# PIC32MZ_Bare_Bones.net
KiCad netlist of a schematic drawn in EAGLE
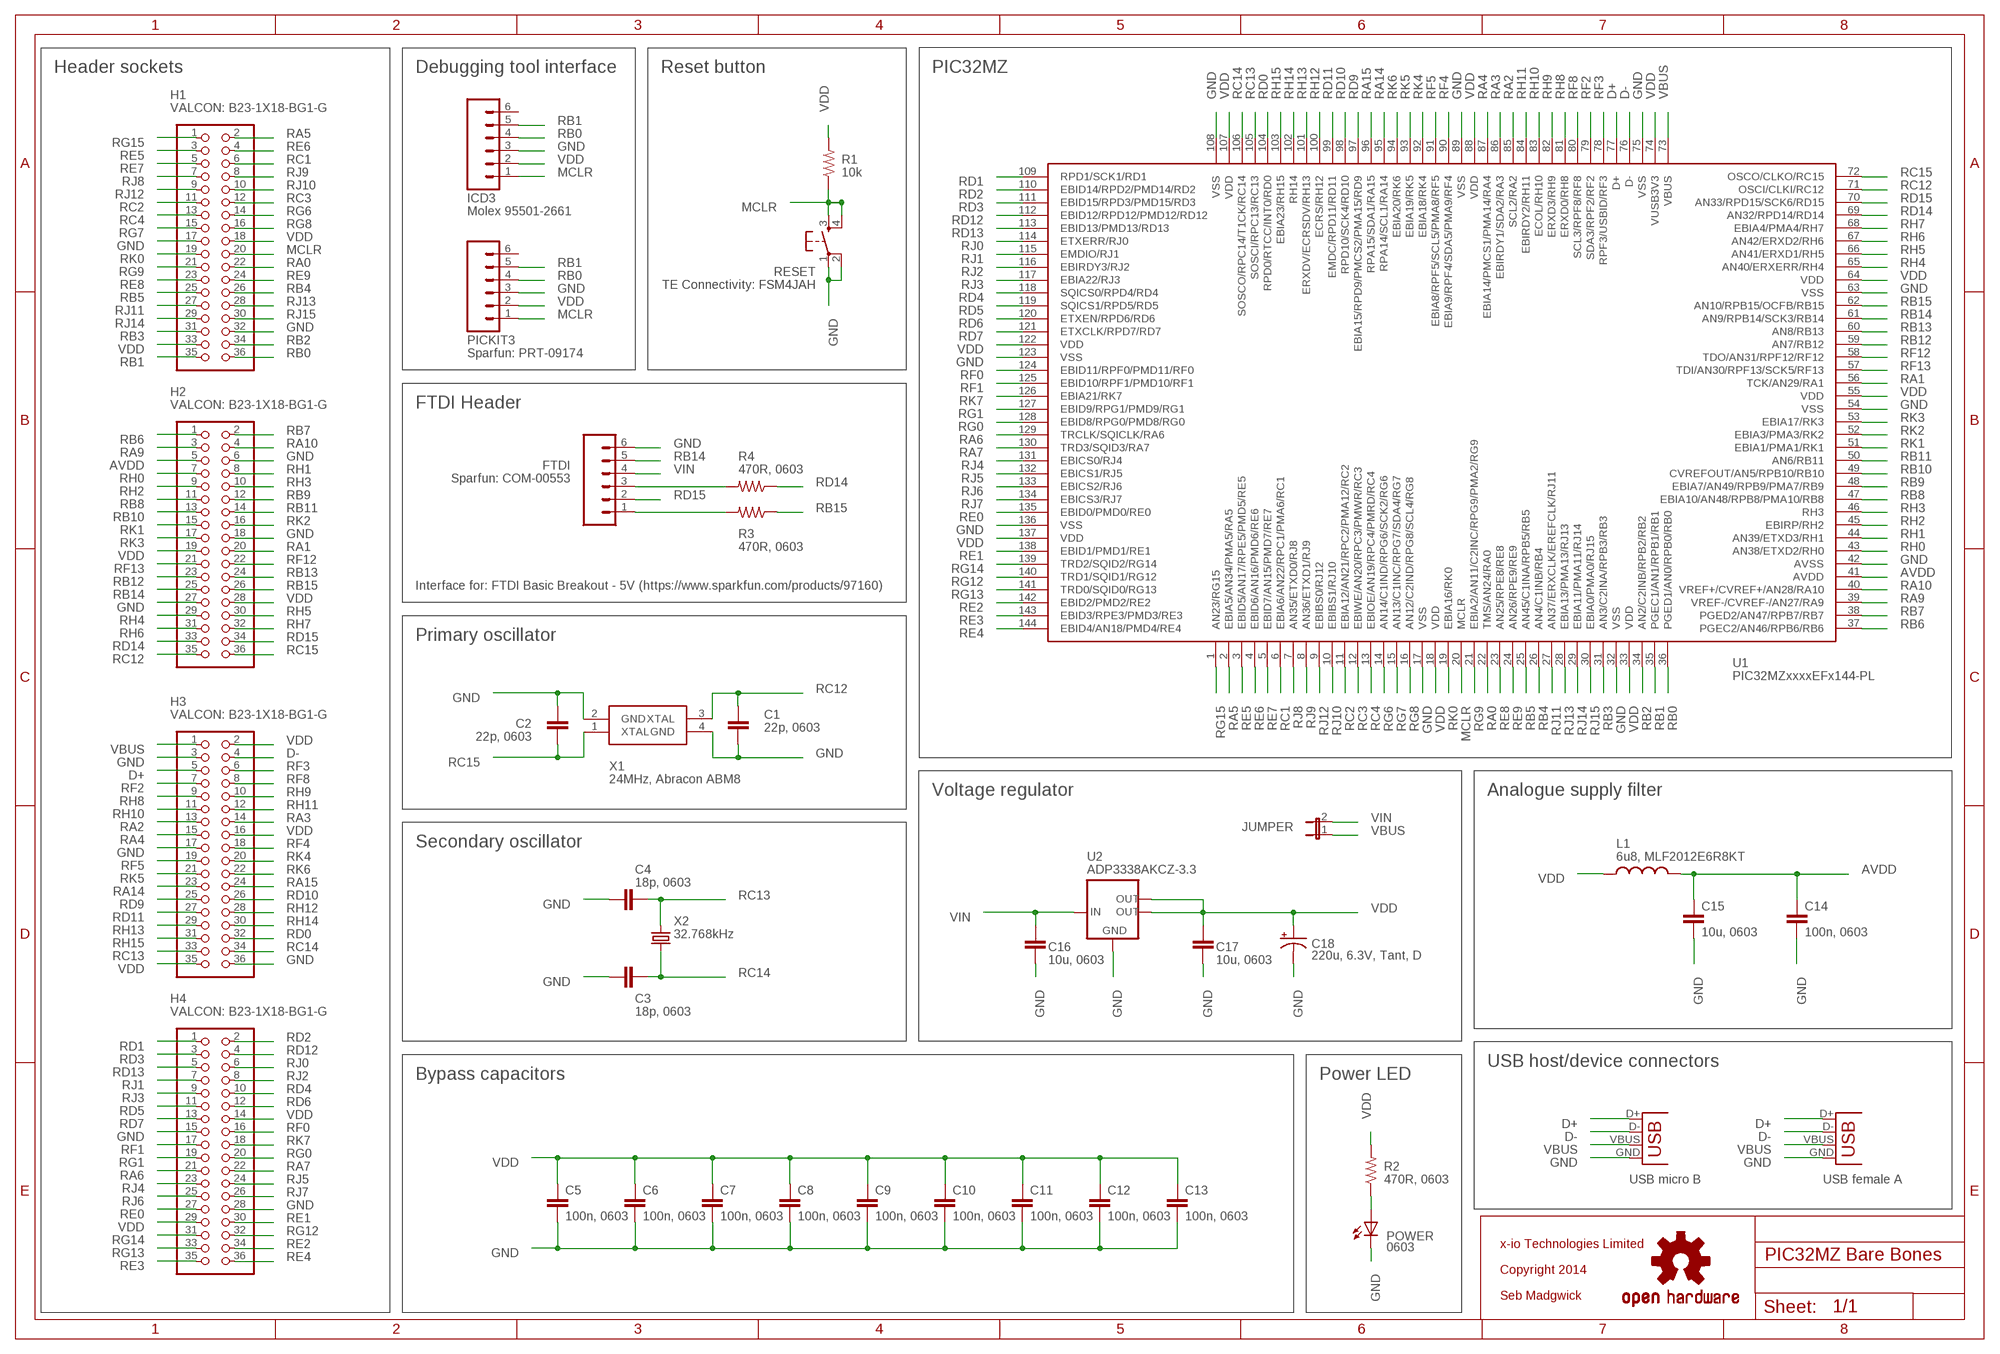
[diagram p0: schematic, sheet 1]

(export (version "E")
  (design (tool "Eeschema 10.0.6"))
  (components
    (comp (ref "C1")
      (value "22p, 0603")
      (footprint "eagle-import:0603-CAP")
      (libsource (lib "eagle-import") (part "CAP0603-CAP"))
    )
    (comp (ref "C2")
      (value "22p, 0603")
      (footprint "eagle-import:0603-CAP")
      (libsource (lib "eagle-import") (part "CAP0603-CAP"))
    )
    (comp (ref "C3")
      (value "18p, 0603")
      (footprint "eagle-import:0603-CAP")
      (libsource (lib "eagle-import") (part "CAP0603-CAP"))
    )
    (comp (ref "C4")
      (value "18p, 0603")
      (footprint "eagle-import:0603-CAP")
      (libsource (lib "eagle-import") (part "CAP0603-CAP"))
    )
    (comp (ref "C5")
      (value "100n, 0603")
      (footprint "eagle-import:0603-CAP")
      (libsource (lib "eagle-import") (part "CAP0603-CAP"))
    )
    (comp (ref "C6")
      (value "100n, 0603")
      (footprint "eagle-import:0603-CAP")
      (libsource (lib "eagle-import") (part "CAP0603-CAP"))
    )
    (comp (ref "C7")
      (value "100n, 0603")
      (footprint "eagle-import:0603-CAP")
      (libsource (lib "eagle-import") (part "CAP0603-CAP"))
    )
    (comp (ref "C8")
      (value "100n, 0603")
      (footprint "eagle-import:0603-CAP")
      (libsource (lib "eagle-import") (part "CAP0603-CAP"))
    )
    (comp (ref "C9")
      (value "100n, 0603")
      (footprint "eagle-import:0603-CAP")
      (libsource (lib "eagle-import") (part "CAP0603-CAP"))
    )
    (comp (ref "C10")
      (value "100n, 0603")
      (footprint "eagle-import:0603-CAP")
      (libsource (lib "eagle-import") (part "CAP0603-CAP"))
    )
    (comp (ref "C11")
      (value "100n, 0603")
      (footprint "eagle-import:0603-CAP")
      (libsource (lib "eagle-import") (part "CAP0603-CAP"))
    )
    (comp (ref "C12")
      (value "100n, 0603")
      (footprint "eagle-import:0603-CAP")
      (libsource (lib "eagle-import") (part "CAP0603-CAP"))
    )
    (comp (ref "C13")
      (value "100n, 0603")
      (footprint "eagle-import:0603-CAP")
      (libsource (lib "eagle-import") (part "CAP0603-CAP"))
    )
    (comp (ref "C14")
      (value "100n, 0603")
      (footprint "eagle-import:0603-CAP")
      (libsource (lib "eagle-import") (part "CAP0603-CAP"))
    )
    (comp (ref "C15")
      (value "10u, 0603")
      (footprint "eagle-import:0603-CAP")
      (libsource (lib "eagle-import") (part "CAP0603-CAP"))
    )
    (comp (ref "C16")
      (value "10u, 0603")
      (footprint "eagle-import:0603-CAP")
      (libsource (lib "eagle-import") (part "CAP0603-CAP"))
    )
    (comp (ref "C17")
      (value "10u, 0603")
      (footprint "eagle-import:0603-CAP")
      (libsource (lib "eagle-import") (part "CAP0603-CAP"))
    )
    (comp (ref "C18")
      (value "220u, 6.3V, Tant, D")
      (footprint "eagle-import:SMC_D")
      (libsource (lib "eagle-import") (part "CPOL-USSMCD"))
    )
    (comp (ref "FTDI")
      (value "Sparfun: COM-00553")
      (footprint "eagle-import:1X06")
      (libsource (lib "eagle-import") (part "M06SIP"))
    )
    (comp (ref "H1")
      (value "VALCON: B23-1X18-BG1-G")
      (footprint "eagle-import:2X18")
      (libsource (lib "eagle-import") (part "PINHD-2X18"))
    )
    (comp (ref "H2")
      (value "VALCON: B23-1X18-BG1-G")
      (footprint "eagle-import:2X18")
      (libsource (lib "eagle-import") (part "PINHD-2X18"))
    )
    (comp (ref "H3")
      (value "VALCON: B23-1X18-BG1-G")
      (footprint "eagle-import:2X18")
      (libsource (lib "eagle-import") (part "PINHD-2X18"))
    )
    (comp (ref "H4")
      (value "VALCON: B23-1X18-BG1-G")
      (footprint "eagle-import:2X18")
      (libsource (lib "eagle-import") (part "PINHD-2X18"))
    )
    (comp (ref "ICD3")
      (value "Molex 95501-2661")
      (footprint "eagle-import:RJ11-6")
      (libsource (lib "eagle-import") (part "RJ11-6PTH"))
    )
    (comp (ref "JUMPER")
      (value "JUMPER-2SMD-NO")
      (footprint "eagle-import:SJ_2S-NO")
      (libsource (lib "eagle-import") (part "JUMPER-2SMD-NO"))
    )
    (comp (ref "L1")
      (value "6u8, MLF2012E6R8KT")
      (footprint "eagle-import:1007")
      (libsource (lib "eagle-import") (part "INDUCTOR1007"))
    )
    (comp (ref "PICKIT3")
      (value "Sparfun: PRT-09174")
      (footprint "eagle-import:1X06")
      (libsource (lib "eagle-import") (part "M06SIP"))
    )
    (comp (ref "POWER")
      (value "0603")
      (footprint "eagle-import:LED-0603")
      (libsource (lib "eagle-import") (part "LED0603"))
    )
    (comp (ref "R1")
      (value "10k")
      (footprint "eagle-import:0603-RES")
      (libsource (lib "eagle-import") (part "RESISTOR0603-RES"))
    )
    (comp (ref "R2")
      (value "470R, 0603")
      (footprint "eagle-import:0603-RES")
      (libsource (lib "eagle-import") (part "RESISTOR0603-RES"))
    )
    (comp (ref "R3")
      (value "470R, 0603")
      (footprint "eagle-import:0603-RES")
      (libsource (lib "eagle-import") (part "RESISTOR0603-RES"))
    )
    (comp (ref "R4")
      (value "470R, 0603")
      (footprint "eagle-import:0603-RES")
      (libsource (lib "eagle-import") (part "RESISTOR0603-RES"))
    )
    (comp (ref "RESET")
      (value "TE Connectivity: FSM4JAH")
      (footprint "eagle-import:TACTILE-PTH")
      (libsource (lib "eagle-import") (part "TAC_SWITCHPTH"))
    )
    (comp (ref "U$4")
      (value "OSHW-LOGOS")
      (footprint "eagle-import:OSHW-LOGO-S")
      (libsource (lib "eagle-import") (part "OSHW-LOGOS"))
    )
    (comp (ref "U1")
      (value "PIC32MZxxxxEFx144-PL")
      (footprint "eagle-import:LQFP144")
      (libsource (lib "eagle-import") (part "PIC32MZ2048EC(G/H/M)144-PL"))
    )
    (comp (ref "U2")
      (value "ADP3338AKCZ-3.3")
      (footprint "eagle-import:SOT223")
      (libsource (lib "eagle-import") (part "ADP3338"))
    )
    (comp (ref "X1")
      (value "24MHz, Abracon ABM8")
      (footprint "eagle-import:ABM8")
      (libsource (lib "eagle-import") (part "ABM8"))
    )
    (comp (ref "X2")
      (value "32.768kHz")
      (footprint "eagle-import:TC26H")
      (libsource (lib "eagle-import") (part "CRYSTALTC26H"))
    )
    (comp (ref "X3")
      (value "USB-MICROB")
      (footprint "eagle-import:USB-MICROB")
      (libsource (lib "eagle-import") (part "USB-MICROB"))
    )
    (comp (ref "X4")
      (value "USB-A-SMD")
      (footprint "eagle-import:USB-A-S-NOSILK-FEMALE")
      (libsource (lib "eagle-import") (part "USB-A-SMD"))
    )
  )
  (nets
    (net (code "1") (name "/AVDD") (class "Default")
      (node (ref "C14") (pin "1") (pinfunction "1_1") (pintype "passive"))
      (node (ref "C15") (pin "1") (pinfunction "1_1") (pintype "passive"))
      (node (ref "H2") (pin "5") (pinfunction "5_5") (pintype "passive"))
      (node (ref "L1") (pin "2") (pinfunction "2_2") (pintype "passive"))
      (node (ref "U1") (pin "41") (pinfunction "AVDD_41") (pintype "bidirectional"))
    )
    (net (code "2") (name "/D+") (class "Default")
      (node (ref "H3") (pin "5") (pinfunction "5_5") (pintype "passive"))
      (node (ref "U1") (pin "77") (pinfunction "D+_77") (pintype "bidirectional"))
      (node (ref "X3") (pin "D+") (pinfunction "D+_D+") (pintype "bidirectional"))
      (node (ref "X4") (pin "D+") (pinfunction "D+_D+") (pintype "bidirectional"))
    )
    (net (code "3") (name "/D-") (class "Default")
      (node (ref "H3") (pin "4") (pinfunction "4_4") (pintype "passive"))
      (node (ref "U1") (pin "76") (pinfunction "D-_76") (pintype "bidirectional"))
      (node (ref "X3") (pin "D-") (pinfunction "D-_D-") (pintype "bidirectional"))
      (node (ref "X4") (pin "D-") (pinfunction "D-_D-") (pintype "bidirectional"))
    )
    (net (code "4") (name "/GND") (class "Default")
      (node (ref "C1") (pin "2") (pinfunction "2_2") (pintype "passive"))
      (node (ref "C10") (pin "2") (pinfunction "2_2") (pintype "passive"))
      (node (ref "C11") (pin "2") (pinfunction "2_2") (pintype "passive"))
      (node (ref "C12") (pin "2") (pinfunction "2_2") (pintype "passive"))
      (node (ref "C13") (pin "2") (pinfunction "2_2") (pintype "passive"))
      (node (ref "C14") (pin "2") (pinfunction "2_2") (pintype "passive"))
      (node (ref "C15") (pin "2") (pinfunction "2_2") (pintype "passive"))
      (node (ref "C16") (pin "2") (pinfunction "2_2") (pintype "passive"))
      (node (ref "C17") (pin "2") (pinfunction "2_2") (pintype "passive"))
      (node (ref "C18") (pin "-") (pinfunction "-_-") (pintype "passive"))
      (node (ref "C2") (pin "1") (pinfunction "1_1") (pintype "passive"))
      (node (ref "C3") (pin "2") (pinfunction "2_2") (pintype "passive"))
      (node (ref "C4") (pin "2") (pinfunction "2_2") (pintype "passive"))
      (node (ref "C5") (pin "2") (pinfunction "2_2") (pintype "passive"))
      (node (ref "C6") (pin "2") (pinfunction "2_2") (pintype "passive"))
      (node (ref "C7") (pin "2") (pinfunction "2_2") (pintype "passive"))
      (node (ref "C8") (pin "2") (pinfunction "2_2") (pintype "passive"))
      (node (ref "C9") (pin "2") (pinfunction "2_2") (pintype "passive"))
      (node (ref "FTDI") (pin "6") (pinfunction "6_6") (pintype "passive"))
      (node (ref "H1") (pin "17") (pinfunction "17_17") (pintype "passive"))
      (node (ref "H1") (pin "32") (pinfunction "32_32") (pintype "passive"))
      (node (ref "H2") (pin "18") (pinfunction "18_18") (pintype "passive"))
      (node (ref "H2") (pin "27") (pinfunction "27_27") (pintype "passive"))
      (node (ref "H2") (pin "6") (pinfunction "6_6") (pintype "passive"))
      (node (ref "H3") (pin "17") (pinfunction "17_17") (pintype "passive"))
      (node (ref "H3") (pin "3") (pinfunction "3_3") (pintype "passive"))
      (node (ref "H3") (pin "36") (pinfunction "36_36") (pintype "passive"))
      (node (ref "H4") (pin "15") (pinfunction "15_15") (pintype "passive"))
      (node (ref "H4") (pin "28") (pinfunction "28_28") (pintype "passive"))
      (node (ref "ICD3") (pin "3") (pinfunction "3_3") (pintype "passive"))
      (node (ref "PICKIT3") (pin "3") (pinfunction "3_3") (pintype "passive"))
      (node (ref "POWER") (pin "C") (pinfunction "C_C") (pintype "passive"))
      (node (ref "RESET") (pin "1") (pinfunction "1_1") (pintype "passive"))
      (node (ref "RESET") (pin "2") (pinfunction "2_2") (pintype "passive"))
      (node (ref "U1") (pin "108") (pinfunction "VSS_108") (pintype "bidirectional"))
      (node (ref "U1") (pin "123") (pinfunction "VSS_123") (pintype "bidirectional"))
      (node (ref "U1") (pin "136") (pinfunction "VSS_136") (pintype "bidirectional"))
      (node (ref "U1") (pin "17") (pinfunction "VSS_17") (pintype "bidirectional"))
      (node (ref "U1") (pin "32") (pinfunction "VSS_32") (pintype "bidirectional"))
      (node (ref "U1") (pin "42") (pinfunction "AVSS_42") (pintype "bidirectional"))
      (node (ref "U1") (pin "54") (pinfunction "VSS_54") (pintype "bidirectional"))
      (node (ref "U1") (pin "63") (pinfunction "VSS_63") (pintype "bidirectional"))
      (node (ref "U1") (pin "75") (pinfunction "VSS_75") (pintype "bidirectional"))
      (node (ref "U1") (pin "89") (pinfunction "VSS_89") (pintype "bidirectional"))
      (node (ref "U2") (pin "1") (pinfunction "GND_1") (pintype "input"))
      (node (ref "X1") (pin "2") (pinfunction "GND_2") (pintype "bidirectional"))
      (node (ref "X1") (pin "4") (pinfunction "GND_4") (pintype "bidirectional"))
      (node (ref "X3") (pin "GND") (pinfunction "GND_GND") (pintype "bidirectional"))
      (node (ref "X4") (pin "GND") (pinfunction "GND_GND") (pintype "bidirectional"))
    )
    (net (code "5") (name "/MCLR") (class "Default")
      (node (ref "H1") (pin "20") (pinfunction "20_20") (pintype "passive"))
      (node (ref "ICD3") (pin "1") (pinfunction "1_1") (pintype "passive"))
      (node (ref "PICKIT3") (pin "1") (pinfunction "1_1") (pintype "passive"))
      (node (ref "R1") (pin "1") (pinfunction "1_1") (pintype "passive"))
      (node (ref "RESET") (pin "3") (pinfunction "3_3") (pintype "passive"))
      (node (ref "RESET") (pin "4") (pinfunction "4_4") (pintype "passive"))
      (node (ref "U1") (pin "20") (pinfunction "MCLR_20") (pintype "bidirectional"))
    )
    (net (code "6") (name "/RA0") (class "Default")
      (node (ref "H1") (pin "22") (pinfunction "22_22") (pintype "passive"))
      (node (ref "U1") (pin "22") (pinfunction "TMS/AN24/RA0_22") (pintype "bidirectional"))
    )
    (net (code "7") (name "/RA1") (class "Default")
      (node (ref "H2") (pin "20") (pinfunction "20_20") (pintype "passive"))
      (node (ref "U1") (pin "56") (pinfunction "TCK/AN29/RA1_56") (pintype "bidirectional"))
    )
    (net (code "8") (name "/RA2") (class "Default")
      (node (ref "H3") (pin "13") (pinfunction "13_13") (pintype "passive"))
      (node (ref "U1") (pin "85") (pinfunction "SCL2/RA2_85") (pintype "bidirectional"))
    )
    (net (code "9") (name "/RA3") (class "Default")
      (node (ref "H3") (pin "14") (pinfunction "14_14") (pintype "passive"))
      (node (ref "U1") (pin "86") (pinfunction "EBIRDY1/SDA2/RA3_86") (pintype "bidirectional"))
    )
    (net (code "10") (name "/RA4") (class "Default")
      (node (ref "H3") (pin "15") (pinfunction "15_15") (pintype "passive"))
      (node (ref "U1") (pin "87") (pinfunction "EBIA14/PMCS1/PMA14/RA4_87") (pintype "bidirectional"))
    )
    (net (code "11") (name "/RA5") (class "Default")
      (node (ref "H1") (pin "2") (pinfunction "2_2") (pintype "passive"))
      (node (ref "U1") (pin "2") (pinfunction "EBIA5/AN34/PMA5/RA5_2") (pintype "bidirectional"))
    )
    (net (code "12") (name "/RA6") (class "Default")
      (node (ref "H4") (pin "21") (pinfunction "21_21") (pintype "passive"))
      (node (ref "U1") (pin "129") (pinfunction "TRCLK/SQICLK/RA6_129") (pintype "bidirectional"))
    )
    (net (code "13") (name "/RA7") (class "Default")
      (node (ref "H4") (pin "22") (pinfunction "22_22") (pintype "passive"))
      (node (ref "U1") (pin "130") (pinfunction "TRD3/SQID3/RA7_130") (pintype "bidirectional"))
    )
    (net (code "14") (name "/RA9") (class "Default")
      (node (ref "H2") (pin "3") (pinfunction "3_3") (pintype "passive"))
      (node (ref "U1") (pin "39") (pinfunction "VREF-/CVREF-/AN27/RA9_39") (pintype "bidirectional"))
    )
    (net (code "15") (name "/RA10") (class "Default")
      (node (ref "H2") (pin "4") (pinfunction "4_4") (pintype "passive"))
      (node (ref "U1") (pin "40") (pinfunction "VREF+/CVREF+/AN28/RA10_40") (pintype "bidirectional"))
    )
    (net (code "16") (name "/RA14") (class "Default")
      (node (ref "H3") (pin "23") (pinfunction "23_23") (pintype "passive"))
      (node (ref "U1") (pin "95") (pinfunction "RPA14/SCL1/RA14_95") (pintype "bidirectional"))
    )
    (net (code "17") (name "/RA15") (class "Default")
      (node (ref "H3") (pin "24") (pinfunction "24_24") (pintype "passive"))
      (node (ref "U1") (pin "96") (pinfunction "RPA15/SDA1/RA15_96") (pintype "bidirectional"))
    )
    (net (code "18") (name "/RB0") (class "Default")
      (node (ref "H1") (pin "36") (pinfunction "36_36") (pintype "passive"))
      (node (ref "ICD3") (pin "4") (pinfunction "4_4") (pintype "passive"))
      (node (ref "PICKIT3") (pin "4") (pinfunction "4_4") (pintype "passive"))
      (node (ref "U1") (pin "36") (pinfunction "PGED1/AN0/RPB0/RB0_36") (pintype "bidirectional"))
    )
    (net (code "19") (name "/RB1") (class "Default")
      (node (ref "H1") (pin "35") (pinfunction "35_35") (pintype "passive"))
      (node (ref "ICD3") (pin "5") (pinfunction "5_5") (pintype "passive"))
      (node (ref "PICKIT3") (pin "5") (pinfunction "5_5") (pintype "passive"))
      (node (ref "U1") (pin "35") (pinfunction "PGEC1/AN1/RPB1/RB1_35") (pintype "bidirectional"))
    )
    (net (code "20") (name "/RB2") (class "Default")
      (node (ref "H1") (pin "34") (pinfunction "34_34") (pintype "passive"))
      (node (ref "U1") (pin "34") (pinfunction "AN2/C2INB/RPB2/RB2_34") (pintype "bidirectional"))
    )
    (net (code "21") (name "/RB3") (class "Default")
      (node (ref "H1") (pin "31") (pinfunction "31_31") (pintype "passive"))
      (node (ref "U1") (pin "31") (pinfunction "AN3/C2INA/RPB3/RB3_31") (pintype "bidirectional"))
    )
    (net (code "22") (name "/RB4") (class "Default")
      (node (ref "H1") (pin "26") (pinfunction "26_26") (pintype "passive"))
      (node (ref "U1") (pin "26") (pinfunction "AN4/C1INB/RB4_26") (pintype "bidirectional"))
    )
    (net (code "23") (name "/RB5") (class "Default")
      (node (ref "H1") (pin "25") (pinfunction "25_25") (pintype "passive"))
      (node (ref "U1") (pin "25") (pinfunction "AN45/C1INA/RPB5/RB5_25") (pintype "bidirectional"))
    )
    (net (code "24") (name "/RB6") (class "Default")
      (node (ref "H2") (pin "1") (pinfunction "1_1") (pintype "passive"))
      (node (ref "U1") (pin "37") (pinfunction "PGEC2/AN46/RPB6/RB6_37") (pintype "bidirectional"))
    )
    (net (code "25") (name "/RB7") (class "Default")
      (node (ref "H2") (pin "2") (pinfunction "2_2") (pintype "passive"))
      (node (ref "U1") (pin "38") (pinfunction "PGED2/AN47/RPB7/RB7_38") (pintype "bidirectional"))
    )
    (net (code "26") (name "/RB8") (class "Default")
      (node (ref "H2") (pin "11") (pinfunction "11_11") (pintype "passive"))
      (node (ref "U1") (pin "47") (pinfunction "EBIA10/AN48/RPB8/PMA10/RB8_47") (pintype "bidirectional"))
    )
    (net (code "27") (name "/RB9") (class "Default")
      (node (ref "H2") (pin "12") (pinfunction "12_12") (pintype "passive"))
      (node (ref "U1") (pin "48") (pinfunction "EBIA7/AN49/RPB9/PMA7/RB9_48") (pintype "bidirectional"))
    )
    (net (code "28") (name "/RB10") (class "Default")
      (node (ref "H2") (pin "13") (pinfunction "13_13") (pintype "passive"))
      (node (ref "U1") (pin "49") (pinfunction "CVREFOUT/AN5/RPB10/RB10_49") (pintype "bidirectional"))
    )
    (net (code "29") (name "/RB11") (class "Default")
      (node (ref "H2") (pin "14") (pinfunction "14_14") (pintype "passive"))
      (node (ref "U1") (pin "50") (pinfunction "AN6/RB11_50") (pintype "bidirectional"))
    )
    (net (code "30") (name "/RB12") (class "Default")
      (node (ref "H2") (pin "23") (pinfunction "23_23") (pintype "passive"))
      (node (ref "U1") (pin "59") (pinfunction "AN7/RB12_59") (pintype "bidirectional"))
    )
    (net (code "31") (name "/RB13") (class "Default")
      (node (ref "H2") (pin "24") (pinfunction "24_24") (pintype "passive"))
      (node (ref "U1") (pin "60") (pinfunction "AN8/RB13_60") (pintype "bidirectional"))
    )
    (net (code "32") (name "/RB14") (class "Default")
      (node (ref "FTDI") (pin "5") (pinfunction "5_5") (pintype "passive"))
      (node (ref "H2") (pin "25") (pinfunction "25_25") (pintype "passive"))
      (node (ref "U1") (pin "61") (pinfunction "AN9/RPB14/SCK3/RB14_61") (pintype "bidirectional"))
    )
    (net (code "33") (name "/RB15") (class "Default")
      (node (ref "H2") (pin "26") (pinfunction "26_26") (pintype "passive"))
      (node (ref "R3") (pin "1") (pinfunction "1_1") (pintype "passive"))
      (node (ref "U1") (pin "62") (pinfunction "AN10/RPB15/OCFB/RB15_62") (pintype "bidirectional"))
    )
    (net (code "34") (name "/RC1") (class "Default")
      (node (ref "H1") (pin "6") (pinfunction "6_6") (pintype "passive"))
      (node (ref "U1") (pin "6") (pinfunction "EBIA6/AN22/RPC1/PMA6/RC1_6") (pintype "bidirectional"))
    )
    (net (code "35") (name "/RC2") (class "Default")
      (node (ref "H1") (pin "11") (pinfunction "11_11") (pintype "passive"))
      (node (ref "U1") (pin "11") (pinfunction "EBIA12/AN21/RPC2/PMA12/RC2_11") (pintype "bidirectional"))
    )
    (net (code "36") (name "/RC3") (class "Default")
      (node (ref "H1") (pin "12") (pinfunction "12_12") (pintype "passive"))
      (node (ref "U1") (pin "12") (pinfunction "EBIWE/AN20/RPC3/PMWR/RC3_12") (pintype "bidirectional"))
    )
    (net (code "37") (name "/RC4") (class "Default")
      (node (ref "H1") (pin "13") (pinfunction "13_13") (pintype "passive"))
      (node (ref "U1") (pin "13") (pinfunction "EBIOE/AN19/RPC4/PMRD/RC4_13") (pintype "bidirectional"))
    )
    (net (code "38") (name "/RC12") (class "Default")
      (node (ref "C1") (pin "1") (pinfunction "1_1") (pintype "passive"))
      (node (ref "H2") (pin "35") (pinfunction "35_35") (pintype "passive"))
      (node (ref "U1") (pin "71") (pinfunction "OSCI/CLKI/RC12_71") (pintype "bidirectional"))
      (node (ref "X1") (pin "3") (pinfunction "XTAL_3") (pintype "bidirectional"))
    )
    (net (code "39") (name "/RC13") (class "Default")
      (node (ref "C4") (pin "1") (pinfunction "1_1") (pintype "passive"))
      (node (ref "H3") (pin "33") (pinfunction "33_33") (pintype "passive"))
      (node (ref "U1") (pin "105") (pinfunction "SOSCI/RPC13/RC13_105") (pintype "bidirectional"))
      (node (ref "X2") (pin "1") (pinfunction "1_1") (pintype "passive"))
    )
    (net (code "40") (name "/RC14") (class "Default")
      (node (ref "C3") (pin "1") (pinfunction "1_1") (pintype "passive"))
      (node (ref "H3") (pin "34") (pinfunction "34_34") (pintype "passive"))
      (node (ref "U1") (pin "106") (pinfunction "SOSCO/RPC14/T1CK/RC14_106") (pintype "bidirectional"))
      (node (ref "X2") (pin "2") (pinfunction "2_2") (pintype "passive"))
    )
    (net (code "41") (name "/RC15") (class "Default")
      (node (ref "C2") (pin "2") (pinfunction "2_2") (pintype "passive"))
      (node (ref "H2") (pin "36") (pinfunction "36_36") (pintype "passive"))
      (node (ref "U1") (pin "72") (pinfunction "OSCO/CLKO/RC15_72") (pintype "bidirectional"))
      (node (ref "X1") (pin "1") (pinfunction "XTAL_1") (pintype "bidirectional"))
    )
    (net (code "42") (name "/RD0") (class "Default")
      (node (ref "H3") (pin "32") (pinfunction "32_32") (pintype "passive"))
      (node (ref "U1") (pin "104") (pinfunction "RPD0/RTCC/INT0/RD0_104") (pintype "bidirectional"))
    )
    (net (code "43") (name "/RD1") (class "Default")
      (node (ref "H4") (pin "1") (pinfunction "1_1") (pintype "passive"))
      (node (ref "U1") (pin "109") (pinfunction "RPD1/SCK1/RD1_109") (pintype "bidirectional"))
    )
    (net (code "44") (name "/RD2") (class "Default")
      (node (ref "H4") (pin "2") (pinfunction "2_2") (pintype "passive"))
      (node (ref "U1") (pin "110") (pinfunction "EBID14/RPD2/PMD14/RD2_110") (pintype "bidirectional"))
    )
    (net (code "45") (name "/RD3") (class "Default")
      (node (ref "H4") (pin "3") (pinfunction "3_3") (pintype "passive"))
      (node (ref "U1") (pin "111") (pinfunction "EBID15/RPD3/PMD15/RD3_111") (pintype "bidirectional"))
    )
    (net (code "46") (name "/RD4") (class "Default")
      (node (ref "H4") (pin "10") (pinfunction "10_10") (pintype "passive"))
      (node (ref "U1") (pin "118") (pinfunction "SQICS0/RPD4/RD4_118") (pintype "bidirectional"))
    )
    (net (code "47") (name "/RD5") (class "Default")
      (node (ref "H4") (pin "11") (pinfunction "11_11") (pintype "passive"))
      (node (ref "U1") (pin "119") (pinfunction "SQICS1/RPD5/RD5_119") (pintype "bidirectional"))
    )
    (net (code "48") (name "/RD6") (class "Default")
      (node (ref "H4") (pin "12") (pinfunction "12_12") (pintype "passive"))
      (node (ref "U1") (pin "120") (pinfunction "ETXEN/RPD6/RD6_120") (pintype "bidirectional"))
    )
    (net (code "49") (name "/RD7") (class "Default")
      (node (ref "H4") (pin "13") (pinfunction "13_13") (pintype "passive"))
      (node (ref "U1") (pin "121") (pinfunction "ETXCLK/RPD7/RD7_121") (pintype "bidirectional"))
    )
    (net (code "50") (name "/RD9") (class "Default")
      (node (ref "H3") (pin "25") (pinfunction "25_25") (pintype "passive"))
      (node (ref "U1") (pin "97") (pinfunction "EBIA15/RPD9/PMCS2/PMA15/RD9_97") (pintype "bidirectional"))
    )
    (net (code "51") (name "/RD10") (class "Default")
      (node (ref "H3") (pin "26") (pinfunction "26_26") (pintype "passive"))
      (node (ref "U1") (pin "98") (pinfunction "RPD10/SCK4/RD10_98") (pintype "bidirectional"))
    )
    (net (code "52") (name "/RD11") (class "Default")
      (node (ref "H3") (pin "27") (pinfunction "27_27") (pintype "passive"))
      (node (ref "U1") (pin "99") (pinfunction "EMDC/RPD11/RD11_99") (pintype "bidirectional"))
    )
    (net (code "53") (name "/RD12") (class "Default")
      (node (ref "H4") (pin "4") (pinfunction "4_4") (pintype "passive"))
      (node (ref "U1") (pin "112") (pinfunction "EBID12/RPD12/PMD12/RD12_112") (pintype "bidirectional"))
    )
    (net (code "54") (name "/RD13") (class "Default")
      (node (ref "H4") (pin "5") (pinfunction "5_5") (pintype "passive"))
      (node (ref "U1") (pin "113") (pinfunction "EBID13/PMD13/RD13_113") (pintype "bidirectional"))
    )
    (net (code "55") (name "/RD14") (class "Default")
      (node (ref "H2") (pin "33") (pinfunction "33_33") (pintype "passive"))
      (node (ref "R4") (pin "1") (pinfunction "1_1") (pintype "passive"))
      (node (ref "U1") (pin "69") (pinfunction "AN32/RPD14/RD14_69") (pintype "bidirectional"))
    )
    (net (code "56") (name "/RD15") (class "Default")
      (node (ref "FTDI") (pin "2") (pinfunction "2_2") (pintype "passive"))
      (node (ref "H2") (pin "34") (pinfunction "34_34") (pintype "passive"))
      (node (ref "U1") (pin "70") (pinfunction "AN33/RPD15/SCK6/RD15_70") (pintype "bidirectional"))
    )
    (net (code "57") (name "/RE0") (class "Default")
      (node (ref "H4") (pin "27") (pinfunction "27_27") (pintype "passive"))
      (node (ref "U1") (pin "135") (pinfunction "EBID0/PMD0/RE0_135") (pintype "bidirectional"))
    )
    (net (code "58") (name "/RE1") (class "Default")
      (node (ref "H4") (pin "30") (pinfunction "30_30") (pintype "passive"))
      (node (ref "U1") (pin "138") (pinfunction "EBID1/PMD1/RE1_138") (pintype "bidirectional"))
    )
    (net (code "59") (name "/RE2") (class "Default")
      (node (ref "H4") (pin "34") (pinfunction "34_34") (pintype "passive"))
      (node (ref "U1") (pin "142") (pinfunction "EBID2/PMD2/RE2_142") (pintype "bidirectional"))
    )
    (net (code "60") (name "/RE3") (class "Default")
      (node (ref "H4") (pin "35") (pinfunction "35_35") (pintype "passive"))
      (node (ref "U1") (pin "143") (pinfunction "EBID3/RPE3/PMD3/RE3_143") (pintype "bidirectional"))
    )
    (net (code "61") (name "/RE4") (class "Default")
      (node (ref "H4") (pin "36") (pinfunction "36_36") (pintype "passive"))
      (node (ref "U1") (pin "144") (pinfunction "EBID4/AN18/PMD4/RE4_144") (pintype "bidirectional"))
    )
    (net (code "62") (name "/RE5") (class "Default")
      (node (ref "H1") (pin "3") (pinfunction "3_3") (pintype "passive"))
      (node (ref "U1") (pin "3") (pinfunction "EBID5/AN17/RPE5/PMD5/RE5_3") (pintype "bidirectional"))
    )
    (net (code "63") (name "/RE6") (class "Default")
      (node (ref "H1") (pin "4") (pinfunction "4_4") (pintype "passive"))
      (node (ref "U1") (pin "4") (pinfunction "EBID6/AN16/PMD6/RE6_4") (pintype "bidirectional"))
    )
    (net (code "64") (name "/RE7") (class "Default")
      (node (ref "H1") (pin "5") (pinfunction "5_5") (pintype "passive"))
      (node (ref "U1") (pin "5") (pinfunction "EBID7/AN15/PMD7/RE7_5") (pintype "bidirectional"))
    )
    (net (code "65") (name "/RE8") (class "Default")
      (node (ref "H1") (pin "23") (pinfunction "23_23") (pintype "passive"))
      (node (ref "U1") (pin "23") (pinfunction "AN25/RPE8/RE8_23") (pintype "bidirectional"))
    )
    (net (code "66") (name "/RE9") (class "Default")
      (node (ref "H1") (pin "24") (pinfunction "24_24") (pintype "passive"))
      (node (ref "U1") (pin "24") (pinfunction "AN26/RPE9/RE9_24") (pintype "bidirectional"))
    )
    (net (code "67") (name "/RF0") (class "Default")
      (node (ref "H4") (pin "16") (pinfunction "16_16") (pintype "passive"))
      (node (ref "U1") (pin "124") (pinfunction "EBID11/RPF0/PMD11/RF0_124") (pintype "bidirectional"))
    )
    (net (code "68") (name "/RF1") (class "Default")
      (node (ref "H4") (pin "17") (pinfunction "17_17") (pintype "passive"))
      (node (ref "U1") (pin "125") (pinfunction "EBID10/RPF1/PMD10/RF1_125") (pintype "bidirectional"))
    )
    (net (code "69") (name "/RF2") (class "Default")
      (node (ref "H3") (pin "7") (pinfunction "7_7") (pintype "passive"))
      (node (ref "U1") (pin "79") (pinfunction "SDA3/RPF2/RF2_79") (pintype "bidirectional"))
    )
    (net (code "70") (name "/RF3") (class "Default")
      (node (ref "H3") (pin "6") (pinfunction "6_6") (pintype "passive"))
      (node (ref "U1") (pin "78") (pinfunction "RPF3/USBID/RF3_78") (pintype "bidirectional"))
    )
    (net (code "71") (name "/RF4") (class "Default")
      (node (ref "H3") (pin "18") (pinfunction "18_18") (pintype "passive"))
      (node (ref "U1") (pin "90") (pinfunction "EBIA9/RPF4/SDA5/PMA9/RF4_90") (pintype "bidirectional"))
    )
    (net (code "72") (name "/RF5") (class "Default")
      (node (ref "H3") (pin "19") (pinfunction "19_19") (pintype "passive"))
      (node (ref "U1") (pin "91") (pinfunction "EBIA8/RPF5/SCL5/PMA8/RF5_91") (pintype "bidirectional"))
    )
    (net (code "73") (name "/RF8") (class "Default")
      (node (ref "H3") (pin "8") (pinfunction "8_8") (pintype "passive"))
      (node (ref "U1") (pin "80") (pinfunction "SCL3/RPF8/RF8_80") (pintype "bidirectional"))
    )
    (net (code "74") (name "/RF12") (class "Default")
      (node (ref "H2") (pin "22") (pinfunction "22_22") (pintype "passive"))
      (node (ref "U1") (pin "58") (pinfunction "TDO/AN31/RPF12/RF12_58") (pintype "bidirectional"))
    )
    (net (code "75") (name "/RF13") (class "Default")
      (node (ref "H2") (pin "21") (pinfunction "21_21") (pintype "passive"))
      (node (ref "U1") (pin "57") (pinfunction "TDI/AN30/RPF13/SCK5/RF13_57") (pintype "bidirectional"))
    )
    (net (code "76") (name "/RG0") (class "Default")
      (node (ref "H4") (pin "20") (pinfunction "20_20") (pintype "passive"))
      (node (ref "U1") (pin "128") (pinfunction "EBID8/RPG0/PMD8/RG0_128") (pintype "bidirectional"))
    )
    (net (code "77") (name "/RG1") (class "Default")
      (node (ref "H4") (pin "19") (pinfunction "19_19") (pintype "passive"))
      (node (ref "U1") (pin "127") (pinfunction "EBID9/RPG1/PMD9/RG1_127") (pintype "bidirectional"))
    )
    (net (code "78") (name "/RG6") (class "Default")
      (node (ref "H1") (pin "14") (pinfunction "14_14") (pintype "passive"))
      (node (ref "U1") (pin "14") (pinfunction "AN14/C1IND/RPG6/SCK2/RG6_14") (pintype "bidirectional"))
    )
    (net (code "79") (name "/RG7") (class "Default")
      (node (ref "H1") (pin "15") (pinfunction "15_15") (pintype "passive"))
      (node (ref "U1") (pin "15") (pinfunction "AN13/C1INC/RPG7/SDA4/RG7_15") (pintype "bidirectional"))
    )
    (net (code "80") (name "/RG8") (class "Default")
      (node (ref "H1") (pin "16") (pinfunction "16_16") (pintype "passive"))
      (node (ref "U1") (pin "16") (pinfunction "AN12/C2IND/RPG8/SCL4/RG8_16") (pintype "bidirectional"))
    )
    (net (code "81") (name "/RG9") (class "Default")
      (node (ref "H1") (pin "21") (pinfunction "21_21") (pintype "passive"))
      (node (ref "U1") (pin "21") (pinfunction "EBIA2/AN11/C2INC/RPG9/PMA2/RG9_21") (pintype "bidirectional"))
    )
    (net (code "82") (name "/RG12") (class "Default")
      (node (ref "H4") (pin "32") (pinfunction "32_32") (pintype "passive"))
      (node (ref "U1") (pin "140") (pinfunction "TRD1/SQID1/RG12_140") (pintype "bidirectional"))
    )
    (net (code "83") (name "/RG13") (class "Default")
      (node (ref "H4") (pin "33") (pinfunction "33_33") (pintype "passive"))
      (node (ref "U1") (pin "141") (pinfunction "TRD0/SQID0/RG13_141") (pintype "bidirectional"))
    )
    (net (code "84") (name "/RG14") (class "Default")
      (node (ref "H4") (pin "31") (pinfunction "31_31") (pintype "passive"))
      (node (ref "U1") (pin "139") (pinfunction "TRD2/SQID2/RG14_139") (pintype "bidirectional"))
    )
    (net (code "85") (name "/RG15") (class "Default")
      (node (ref "H1") (pin "1") (pinfunction "1_1") (pintype "passive"))
      (node (ref "U1") (pin "1") (pinfunction "AN23/RG15_1") (pintype "bidirectional"))
    )
    (net (code "86") (name "/RH0") (class "Default")
      (node (ref "H2") (pin "7") (pinfunction "7_7") (pintype "passive"))
      (node (ref "U1") (pin "43") (pinfunction "AN38/ETXD2/RH0_43") (pintype "bidirectional"))
    )
    (net (code "87") (name "/RH1") (class "Default")
      (node (ref "H2") (pin "8") (pinfunction "8_8") (pintype "passive"))
      (node (ref "U1") (pin "44") (pinfunction "AN39/ETXD3/RH1_44") (pintype "bidirectional"))
    )
    (net (code "88") (name "/RH2") (class "Default")
      (node (ref "H2") (pin "9") (pinfunction "9_9") (pintype "passive"))
      (node (ref "U1") (pin "45") (pinfunction "EBIRP/RH2_45") (pintype "bidirectional"))
    )
    (net (code "89") (name "/RH3") (class "Default")
      (node (ref "H2") (pin "10") (pinfunction "10_10") (pintype "passive"))
      (node (ref "U1") (pin "46") (pinfunction "RH3_46") (pintype "bidirectional"))
    )
    (net (code "90") (name "/RH4") (class "Default")
      (node (ref "H2") (pin "29") (pinfunction "29_29") (pintype "passive"))
      (node (ref "U1") (pin "65") (pinfunction "AN40/ERXERR/RH4_65") (pintype "bidirectional"))
    )
    (net (code "91") (name "/RH5") (class "Default")
      (node (ref "H2") (pin "30") (pinfunction "30_30") (pintype "passive"))
      (node (ref "U1") (pin "66") (pinfunction "AN41/ERXD1/RH5_66") (pintype "bidirectional"))
    )
    (net (code "92") (name "/RH6") (class "Default")
      (node (ref "H2") (pin "31") (pinfunction "31_31") (pintype "passive"))
      (node (ref "U1") (pin "67") (pinfunction "AN42/ERXD2/RH6_67") (pintype "bidirectional"))
    )
    (net (code "93") (name "/RH7") (class "Default")
      (node (ref "H2") (pin "32") (pinfunction "32_32") (pintype "passive"))
      (node (ref "U1") (pin "68") (pinfunction "EBIA4/PMA4/RH7_68") (pintype "bidirectional"))
    )
    (net (code "94") (name "/RH8") (class "Default")
      (node (ref "H3") (pin "9") (pinfunction "9_9") (pintype "passive"))
      (node (ref "U1") (pin "81") (pinfunction "ERXD0/RH8_81") (pintype "bidirectional"))
    )
    (net (code "95") (name "/RH9") (class "Default")
      (node (ref "H3") (pin "10") (pinfunction "10_10") (pintype "passive"))
      (node (ref "U1") (pin "82") (pinfunction "ERXD3/RH9_82") (pintype "bidirectional"))
    )
    (net (code "96") (name "/RH10") (class "Default")
      (node (ref "H3") (pin "11") (pinfunction "11_11") (pintype "passive"))
      (node (ref "U1") (pin "83") (pinfunction "ECOL/RH10_83") (pintype "bidirectional"))
    )
    (net (code "97") (name "/RH11") (class "Default")
      (node (ref "H3") (pin "12") (pinfunction "12_12") (pintype "passive"))
      (node (ref "U1") (pin "84") (pinfunction "EBIRDY2/RH11_84") (pintype "bidirectional"))
    )
    (net (code "98") (name "/RH12") (class "Default")
      (node (ref "H3") (pin "28") (pinfunction "28_28") (pintype "passive"))
      (node (ref "U1") (pin "100") (pinfunction "ECRS/RH12_100") (pintype "bidirectional"))
    )
    (net (code "99") (name "/RH13") (class "Default")
      (node (ref "H3") (pin "29") (pinfunction "29_29") (pintype "passive"))
      (node (ref "U1") (pin "101") (pinfunction "ERXDV/ECRSDV/RH13_101") (pintype "bidirectional"))
    )
    (net (code "100") (name "/RH14") (class "Default")
      (node (ref "H3") (pin "30") (pinfunction "30_30") (pintype "passive"))
      (node (ref "U1") (pin "102") (pinfunction "RH14_102") (pintype "bidirectional"))
    )
    (net (code "101") (name "/RH15") (class "Default")
      (node (ref "H3") (pin "31") (pinfunction "31_31") (pintype "passive"))
      (node (ref "U1") (pin "103") (pinfunction "EBIA23/RH15_103") (pintype "bidirectional"))
    )
    (net (code "102") (name "/RJ0") (class "Default")
      (node (ref "H4") (pin "6") (pinfunction "6_6") (pintype "passive"))
      (node (ref "U1") (pin "114") (pinfunction "ETXERR/RJ0_114") (pintype "bidirectional"))
    )
    (net (code "103") (name "/RJ1") (class "Default")
      (node (ref "H4") (pin "7") (pinfunction "7_7") (pintype "passive"))
      (node (ref "U1") (pin "115") (pinfunction "EMDIO/RJ1_115") (pintype "bidirectional"))
    )
    (net (code "104") (name "/RJ2") (class "Default")
      (node (ref "H4") (pin "8") (pinfunction "8_8") (pintype "passive"))
      (node (ref "U1") (pin "116") (pinfunction "EBIRDY3/RJ2_116") (pintype "bidirectional"))
    )
    (net (code "105") (name "/RJ3") (class "Default")
      (node (ref "H4") (pin "9") (pinfunction "9_9") (pintype "passive"))
      (node (ref "U1") (pin "117") (pinfunction "EBIA22/RJ3_117") (pintype "bidirectional"))
    )
    (net (code "106") (name "/RJ4") (class "Default")
      (node (ref "H4") (pin "23") (pinfunction "23_23") (pintype "passive"))
      (node (ref "U1") (pin "131") (pinfunction "EBICS0/RJ4_131") (pintype "bidirectional"))
    )
    (net (code "107") (name "/RJ5") (class "Default")
      (node (ref "H4") (pin "24") (pinfunction "24_24") (pintype "passive"))
      (node (ref "U1") (pin "132") (pinfunction "EBICS1/RJ5_132") (pintype "bidirectional"))
    )
    (net (code "108") (name "/RJ6") (class "Default")
      (node (ref "H4") (pin "25") (pinfunction "25_25") (pintype "passive"))
      (node (ref "U1") (pin "133") (pinfunction "EBICS2/RJ6_133") (pintype "bidirectional"))
    )
    (net (code "109") (name "/RJ7") (class "Default")
      (node (ref "H4") (pin "26") (pinfunction "26_26") (pintype "passive"))
      (node (ref "U1") (pin "134") (pinfunction "EBICS3/RJ7_134") (pintype "bidirectional"))
    )
    (net (code "110") (name "/RJ8") (class "Default")
      (node (ref "H1") (pin "7") (pinfunction "7_7") (pintype "passive"))
      (node (ref "U1") (pin "7") (pinfunction "AN35/ETXD0/RJ8_7") (pintype "bidirectional"))
    )
    (net (code "111") (name "/RJ9") (class "Default")
      (node (ref "H1") (pin "8") (pinfunction "8_8") (pintype "passive"))
      (node (ref "U1") (pin "8") (pinfunction "AN36/ETXD1/RJ9_8") (pintype "bidirectional"))
    )
    (net (code "112") (name "/RJ10") (class "Default")
      (node (ref "H1") (pin "10") (pinfunction "10_10") (pintype "passive"))
      (node (ref "U1") (pin "10") (pinfunction "EBIBS1/RJ10_10") (pintype "bidirectional"))
    )
    (net (code "113") (name "/RJ11") (class "Default")
      (node (ref "H1") (pin "27") (pinfunction "27_27") (pintype "passive"))
      (node (ref "U1") (pin "27") (pinfunction "AN37/ERXCLK/EREFCLK/RJ11_27") (pintype "bidirectional"))
    )
    (net (code "114") (name "/RJ12") (class "Default")
      (node (ref "H1") (pin "9") (pinfunction "9_9") (pintype "passive"))
      (node (ref "U1") (pin "9") (pinfunction "EBIBS0/RJ12_9") (pintype "bidirectional"))
    )
    (net (code "115") (name "/RJ13") (class "Default")
      (node (ref "H1") (pin "28") (pinfunction "28_28") (pintype "passive"))
      (node (ref "U1") (pin "28") (pinfunction "EBIA13/PMA13/RJ13_28") (pintype "bidirectional"))
    )
    (net (code "116") (name "/RJ14") (class "Default")
      (node (ref "H1") (pin "29") (pinfunction "29_29") (pintype "passive"))
      (node (ref "U1") (pin "29") (pinfunction "EBIA11/PMA11/RJ14_29") (pintype "bidirectional"))
    )
    (net (code "117") (name "/RJ15") (class "Default")
      (node (ref "H1") (pin "30") (pinfunction "30_30") (pintype "passive"))
      (node (ref "U1") (pin "30") (pinfunction "EBIA0/PMA0/RJ15_30") (pintype "bidirectional"))
    )
    (net (code "118") (name "/RK0") (class "Default")
      (node (ref "H1") (pin "19") (pinfunction "19_19") (pintype "passive"))
      (node (ref "U1") (pin "19") (pinfunction "EBIA16/RK0_19") (pintype "bidirectional"))
    )
    (net (code "119") (name "/RK1") (class "Default")
      (node (ref "H2") (pin "15") (pinfunction "15_15") (pintype "passive"))
      (node (ref "U1") (pin "51") (pinfunction "EBIA1/PMA1/RK1_51") (pintype "bidirectional"))
    )
    (net (code "120") (name "/RK2") (class "Default")
      (node (ref "H2") (pin "16") (pinfunction "16_16") (pintype "passive"))
      (node (ref "U1") (pin "52") (pinfunction "EBIA3/PMA3/RK2_52") (pintype "bidirectional"))
    )
    (net (code "121") (name "/RK3") (class "Default")
      (node (ref "H2") (pin "17") (pinfunction "17_17") (pintype "passive"))
      (node (ref "U1") (pin "53") (pinfunction "EBIA17/RK3_53") (pintype "bidirectional"))
    )
    (net (code "122") (name "/RK4") (class "Default")
      (node (ref "H3") (pin "20") (pinfunction "20_20") (pintype "passive"))
      (node (ref "U1") (pin "92") (pinfunction "EBIA18/RK4_92") (pintype "bidirectional"))
    )
    (net (code "123") (name "/RK5") (class "Default")
      (node (ref "H3") (pin "21") (pinfunction "21_21") (pintype "passive"))
      (node (ref "U1") (pin "93") (pinfunction "EBIA19/RK5_93") (pintype "bidirectional"))
    )
    (net (code "124") (name "/RK6") (class "Default")
      (node (ref "H3") (pin "22") (pinfunction "22_22") (pintype "passive"))
      (node (ref "U1") (pin "94") (pinfunction "EBIA20/RK6_94") (pintype "bidirectional"))
    )
    (net (code "125") (name "/RK7") (class "Default")
      (node (ref "H4") (pin "18") (pinfunction "18_18") (pintype "passive"))
      (node (ref "U1") (pin "126") (pinfunction "EBIA21/RK7_126") (pintype "bidirectional"))
    )
    (net (code "126") (name "/VBUS") (class "Default")
      (node (ref "H3") (pin "1") (pinfunction "1_1") (pintype "passive"))
      (node (ref "JUMPER") (pin "1") (pinfunction "1_1") (pintype "passive"))
      (node (ref "U1") (pin "73") (pinfunction "VBUS_73") (pintype "bidirectional"))
      (node (ref "X3") (pin "VBUS") (pinfunction "VBUS_VBUS") (pintype "bidirectional"))
      (node (ref "X4") (pin "VBUS") (pinfunction "VBUS_VBUS") (pintype "bidirectional"))
    )
    (net (code "127") (name "/VDD") (class "Default")
      (node (ref "C10") (pin "1") (pinfunction "1_1") (pintype "passive"))
      (node (ref "C11") (pin "1") (pinfunction "1_1") (pintype "passive"))
      (node (ref "C12") (pin "1") (pinfunction "1_1") (pintype "passive"))
      (node (ref "C13") (pin "1") (pinfunction "1_1") (pintype "passive"))
      (node (ref "C17") (pin "1") (pinfunction "1_1") (pintype "passive"))
      (node (ref "C18") (pin "+") (pinfunction "+_+") (pintype "passive"))
      (node (ref "C5") (pin "1") (pinfunction "1_1") (pintype "passive"))
      (node (ref "C6") (pin "1") (pinfunction "1_1") (pintype "passive"))
      (node (ref "C7") (pin "1") (pinfunction "1_1") (pintype "passive"))
      (node (ref "C8") (pin "1") (pinfunction "1_1") (pintype "passive"))
      (node (ref "C9") (pin "1") (pinfunction "1_1") (pintype "passive"))
      (node (ref "H1") (pin "18") (pinfunction "18_18") (pintype "passive"))
      (node (ref "H1") (pin "33") (pinfunction "33_33") (pintype "passive"))
      (node (ref "H2") (pin "19") (pinfunction "19_19") (pintype "passive"))
      (node (ref "H2") (pin "28") (pinfunction "28_28") (pintype "passive"))
      (node (ref "H3") (pin "16") (pinfunction "16_16") (pintype "passive"))
      (node (ref "H3") (pin "2") (pinfunction "2_2") (pintype "passive"))
      (node (ref "H3") (pin "35") (pinfunction "35_35") (pintype "passive"))
      (node (ref "H4") (pin "14") (pinfunction "14_14") (pintype "passive"))
      (node (ref "H4") (pin "29") (pinfunction "29_29") (pintype "passive"))
      (node (ref "ICD3") (pin "2") (pinfunction "2_2") (pintype "passive"))
      (node (ref "L1") (pin "1") (pinfunction "1_1") (pintype "passive"))
      (node (ref "PICKIT3") (pin "2") (pinfunction "2_2") (pintype "passive"))
      (node (ref "R1") (pin "2") (pinfunction "2_2") (pintype "passive"))
      (node (ref "R2") (pin "2") (pinfunction "2_2") (pintype "passive"))
      (node (ref "U1") (pin "107") (pinfunction "VDD_107") (pintype "bidirectional"))
      (node (ref "U1") (pin "122") (pinfunction "VDD_122") (pintype "bidirectional"))
      (node (ref "U1") (pin "137") (pinfunction "VDD_137") (pintype "bidirectional"))
      (node (ref "U1") (pin "18") (pinfunction "VDD_18") (pintype "bidirectional"))
      (node (ref "U1") (pin "33") (pinfunction "VDD_33") (pintype "bidirectional"))
      (node (ref "U1") (pin "55") (pinfunction "VDD_55") (pintype "bidirectional"))
      (node (ref "U1") (pin "64") (pinfunction "VDD_64") (pintype "bidirectional"))
      (node (ref "U1") (pin "74") (pinfunction "VUSB3V3_74") (pintype "bidirectional"))
      (node (ref "U1") (pin "88") (pinfunction "VDD_88") (pintype "bidirectional"))
      (node (ref "U2") (pin "2") (pinfunction "OUT_2") (pintype "output"))
      (node (ref "U2") (pin "4") (pinfunction "OUT_4") (pintype "output"))
    )
    (net (code "128") (name "/VIN") (class "Default")
      (node (ref "C16") (pin "1") (pinfunction "1_1") (pintype "passive"))
      (node (ref "FTDI") (pin "4") (pinfunction "4_4") (pintype "passive"))
      (node (ref "JUMPER") (pin "2") (pinfunction "2_2") (pintype "passive"))
      (node (ref "U2") (pin "3") (pinfunction "IN_3") (pintype "input"))
    )
    (net (code "129") (name "Net-(FTDI-Pad1)") (class "Default")
      (node (ref "FTDI") (pin "1") (pinfunction "1_1") (pintype "passive"))
      (node (ref "R3") (pin "2") (pinfunction "2_2") (pintype "passive"))
    )
    (net (code "130") (name "Net-(FTDI-Pad3)") (class "Default")
      (node (ref "FTDI") (pin "3") (pinfunction "3_3") (pintype "passive"))
      (node (ref "R4") (pin "2") (pinfunction "2_2") (pintype "passive"))
    )
    (net (code "131") (name "Net-(POWER-PadA)") (class "Default")
      (node (ref "POWER") (pin "A") (pinfunction "A_A") (pintype "passive"))
      (node (ref "R2") (pin "1") (pinfunction "1_1") (pintype "passive"))
    )
    (net (code "132") (name "unconnected-(ICD3-Pad6)") (class "Default")
      (node (ref "ICD3") (pin "6") (pinfunction "6_6") (pintype "passive"))
    )
    (net (code "133") (name "unconnected-(PICKIT3-Pad6)") (class "Default")
      (node (ref "PICKIT3") (pin "6") (pinfunction "6_6") (pintype "passive"))
    )
  )
)
